# COBreplacement.net
KiCad netlist of a schematic drawn in EAGLE
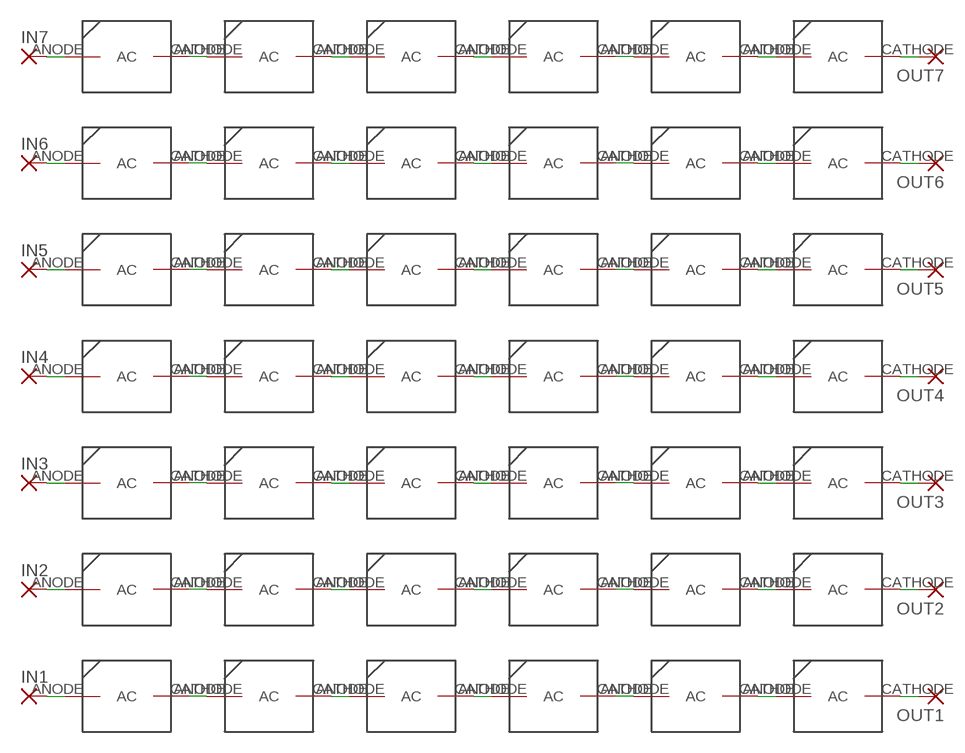
[diagram p0: schematic, sheet 1]

(export (version "E")
  (design (tool "Eeschema 10.0.6"))
  (components
    (comp (ref "IN1")
      (value "SMD2")
      (footprint "eagle-import:SMD1,27-2,54")
      (libsource (lib "eagle-import") (part "SMD2"))
    )
    (comp (ref "IN2")
      (value "SMD2")
      (footprint "eagle-import:SMD1,27-2,54")
      (libsource (lib "eagle-import") (part "SMD2"))
    )
    (comp (ref "IN3")
      (value "SMD2")
      (footprint "eagle-import:SMD1,27-2,54")
      (libsource (lib "eagle-import") (part "SMD2"))
    )
    (comp (ref "IN4")
      (value "SMD2")
      (footprint "eagle-import:SMD1,27-2,54")
      (libsource (lib "eagle-import") (part "SMD2"))
    )
    (comp (ref "IN5")
      (value "SMD2")
      (footprint "eagle-import:SMD1,27-2,54")
      (libsource (lib "eagle-import") (part "SMD2"))
    )
    (comp (ref "IN6")
      (value "SMD2")
      (footprint "eagle-import:SMD1,27-2,54")
      (libsource (lib "eagle-import") (part "SMD2"))
    )
    (comp (ref "IN7")
      (value "SMD2")
      (footprint "eagle-import:SMD1,27-2,54")
      (libsource (lib "eagle-import") (part "SMD2"))
    )
    (comp (ref "OUT1")
      (value "SMD2")
      (footprint "eagle-import:SMD1,27-2,54")
      (libsource (lib "eagle-import") (part "SMD2"))
    )
    (comp (ref "OUT2")
      (value "SMD2")
      (footprint "eagle-import:SMD1,27-2,54")
      (libsource (lib "eagle-import") (part "SMD2"))
    )
    (comp (ref "OUT3")
      (value "SMD2")
      (footprint "eagle-import:SMD1,27-2,54")
      (libsource (lib "eagle-import") (part "SMD2"))
    )
    (comp (ref "OUT4")
      (value "SMD2")
      (footprint "eagle-import:SMD1,27-2,54")
      (libsource (lib "eagle-import") (part "SMD2"))
    )
    (comp (ref "OUT5")
      (value "SMD2")
      (footprint "eagle-import:SMD1,27-2,54")
      (libsource (lib "eagle-import") (part "SMD2"))
    )
    (comp (ref "OUT6")
      (value "SMD2")
      (footprint "eagle-import:SMD1,27-2,54")
      (libsource (lib "eagle-import") (part "SMD2"))
    )
    (comp (ref "OUT7")
      (value "SMD2")
      (footprint "eagle-import:SMD1,27-2,54")
      (libsource (lib "eagle-import") (part "SMD2"))
    )
    (comp (ref "U$1")
      (value "XPE35LED")
      (footprint "eagle-import:XPE35")
      (libsource (lib "eagle-import") (part "XPE35LED"))
    )
    (comp (ref "U$2")
      (value "XPE35LED")
      (footprint "eagle-import:XPE35")
      (libsource (lib "eagle-import") (part "XPE35LED"))
    )
    (comp (ref "U$3")
      (value "XPE35LED")
      (footprint "eagle-import:XPE35")
      (libsource (lib "eagle-import") (part "XPE35LED"))
    )
    (comp (ref "U$4")
      (value "XPE35LED")
      (footprint "eagle-import:XPE35")
      (libsource (lib "eagle-import") (part "XPE35LED"))
    )
    (comp (ref "U$5")
      (value "XPE35LED")
      (footprint "eagle-import:XPE35")
      (libsource (lib "eagle-import") (part "XPE35LED"))
    )
    (comp (ref "U$6")
      (value "XPE35LED")
      (footprint "eagle-import:XPE35")
      (libsource (lib "eagle-import") (part "XPE35LED"))
    )
    (comp (ref "U$7")
      (value "XPE35LED")
      (footprint "eagle-import:XPE35")
      (libsource (lib "eagle-import") (part "XPE35LED"))
    )
    (comp (ref "U$8")
      (value "XPE35LED")
      (footprint "eagle-import:XPE35")
      (libsource (lib "eagle-import") (part "XPE35LED"))
    )
    (comp (ref "U$9")
      (value "XPE35LED")
      (footprint "eagle-import:XPE35")
      (libsource (lib "eagle-import") (part "XPE35LED"))
    )
    (comp (ref "U$10")
      (value "XPE35LED")
      (footprint "eagle-import:XPE35")
      (libsource (lib "eagle-import") (part "XPE35LED"))
    )
    (comp (ref "U$11")
      (value "XPE35LED")
      (footprint "eagle-import:XPE35")
      (libsource (lib "eagle-import") (part "XPE35LED"))
    )
    (comp (ref "U$12")
      (value "XPE35LED")
      (footprint "eagle-import:XPE35")
      (libsource (lib "eagle-import") (part "XPE35LED"))
    )
    (comp (ref "U$13")
      (value "XPE35LED")
      (footprint "eagle-import:XPE35")
      (libsource (lib "eagle-import") (part "XPE35LED"))
    )
    (comp (ref "U$14")
      (value "XPE35LED")
      (footprint "eagle-import:XPE35")
      (libsource (lib "eagle-import") (part "XPE35LED"))
    )
    (comp (ref "U$15")
      (value "XPE35LED")
      (footprint "eagle-import:XPE35")
      (libsource (lib "eagle-import") (part "XPE35LED"))
    )
    (comp (ref "U$16")
      (value "XPE35LED")
      (footprint "eagle-import:XPE35")
      (libsource (lib "eagle-import") (part "XPE35LED"))
    )
    (comp (ref "U$17")
      (value "XPE35LED")
      (footprint "eagle-import:XPE35")
      (libsource (lib "eagle-import") (part "XPE35LED"))
    )
    (comp (ref "U$18")
      (value "XPE35LED")
      (footprint "eagle-import:XPE35")
      (libsource (lib "eagle-import") (part "XPE35LED"))
    )
    (comp (ref "U$19")
      (value "XPE35LED")
      (footprint "eagle-import:XPE35")
      (libsource (lib "eagle-import") (part "XPE35LED"))
    )
    (comp (ref "U$20")
      (value "XPE35LED")
      (footprint "eagle-import:XPE35")
      (libsource (lib "eagle-import") (part "XPE35LED"))
    )
    (comp (ref "U$21")
      (value "XPE35LED")
      (footprint "eagle-import:XPE35")
      (libsource (lib "eagle-import") (part "XPE35LED"))
    )
    (comp (ref "U$22")
      (value "XPE35LED")
      (footprint "eagle-import:XPE35")
      (libsource (lib "eagle-import") (part "XPE35LED"))
    )
    (comp (ref "U$23")
      (value "XPE35LED")
      (footprint "eagle-import:XPE35")
      (libsource (lib "eagle-import") (part "XPE35LED"))
    )
    (comp (ref "U$24")
      (value "XPE35LED")
      (footprint "eagle-import:XPE35")
      (libsource (lib "eagle-import") (part "XPE35LED"))
    )
    (comp (ref "U$25")
      (value "XPE35LED")
      (footprint "eagle-import:XPE35")
      (libsource (lib "eagle-import") (part "XPE35LED"))
    )
    (comp (ref "U$26")
      (value "XPE35LED")
      (footprint "eagle-import:XPE35")
      (libsource (lib "eagle-import") (part "XPE35LED"))
    )
    (comp (ref "U$27")
      (value "XPE35LED")
      (footprint "eagle-import:XPE35")
      (libsource (lib "eagle-import") (part "XPE35LED"))
    )
    (comp (ref "U$28")
      (value "XPE35LED")
      (footprint "eagle-import:XPE35")
      (libsource (lib "eagle-import") (part "XPE35LED"))
    )
    (comp (ref "U$29")
      (value "XPE35LED")
      (footprint "eagle-import:XPE35")
      (libsource (lib "eagle-import") (part "XPE35LED"))
    )
    (comp (ref "U$30")
      (value "XPE35LED")
      (footprint "eagle-import:XPE35")
      (libsource (lib "eagle-import") (part "XPE35LED"))
    )
    (comp (ref "U$31")
      (value "XPE35LED")
      (footprint "eagle-import:XPE35")
      (libsource (lib "eagle-import") (part "XPE35LED"))
    )
    (comp (ref "U$32")
      (value "XPE35LED")
      (footprint "eagle-import:XPE35")
      (libsource (lib "eagle-import") (part "XPE35LED"))
    )
    (comp (ref "U$33")
      (value "XPE35LED")
      (footprint "eagle-import:XPE35")
      (libsource (lib "eagle-import") (part "XPE35LED"))
    )
    (comp (ref "U$34")
      (value "XPE35LED")
      (footprint "eagle-import:XPE35")
      (libsource (lib "eagle-import") (part "XPE35LED"))
    )
    (comp (ref "U$35")
      (value "XPE35LED")
      (footprint "eagle-import:XPE35")
      (libsource (lib "eagle-import") (part "XPE35LED"))
    )
    (comp (ref "U$36")
      (value "XPE35LED")
      (footprint "eagle-import:XPE35")
      (libsource (lib "eagle-import") (part "XPE35LED"))
    )
    (comp (ref "U$37")
      (value "XPE35LED")
      (footprint "eagle-import:XPE35")
      (libsource (lib "eagle-import") (part "XPE35LED"))
    )
    (comp (ref "U$38")
      (value "XPE35LED")
      (footprint "eagle-import:XPE35")
      (libsource (lib "eagle-import") (part "XPE35LED"))
    )
    (comp (ref "U$39")
      (value "XPE35LED")
      (footprint "eagle-import:XPE35")
      (libsource (lib "eagle-import") (part "XPE35LED"))
    )
    (comp (ref "U$40")
      (value "XPE35LED")
      (footprint "eagle-import:XPE35")
      (libsource (lib "eagle-import") (part "XPE35LED"))
    )
    (comp (ref "U$41")
      (value "XPE35LED")
      (footprint "eagle-import:XPE35")
      (libsource (lib "eagle-import") (part "XPE35LED"))
    )
    (comp (ref "U$42")
      (value "XPE35LED")
      (footprint "eagle-import:XPE35")
      (libsource (lib "eagle-import") (part "XPE35LED"))
    )
  )
  (nets
    (net (code "1") (name "Net-(IN1-P)") (class "Default")
      (node (ref "IN1") (pin "1") (pinfunction "P_1") (pintype "passive"))
      (node (ref "U$31") (pin "ANODE") (pinfunction "A_ANODE") (pintype "bidirectional"))
    )
    (net (code "2") (name "Net-(IN2-P)") (class "Default")
      (node (ref "IN2") (pin "1") (pinfunction "P_1") (pintype "passive"))
      (node (ref "U$25") (pin "ANODE") (pinfunction "A_ANODE") (pintype "bidirectional"))
    )
    (net (code "3") (name "Net-(IN3-P)") (class "Default")
      (node (ref "IN3") (pin "1") (pinfunction "P_1") (pintype "passive"))
      (node (ref "U$19") (pin "ANODE") (pinfunction "A_ANODE") (pintype "bidirectional"))
    )
    (net (code "4") (name "Net-(IN4-P)") (class "Default")
      (node (ref "IN4") (pin "1") (pinfunction "P_1") (pintype "passive"))
      (node (ref "U$13") (pin "ANODE") (pinfunction "A_ANODE") (pintype "bidirectional"))
    )
    (net (code "5") (name "Net-(IN5-P)") (class "Default")
      (node (ref "IN5") (pin "1") (pinfunction "P_1") (pintype "passive"))
      (node (ref "U$7") (pin "ANODE") (pinfunction "A_ANODE") (pintype "bidirectional"))
    )
    (net (code "6") (name "Net-(IN6-P)") (class "Default")
      (node (ref "IN6") (pin "1") (pinfunction "P_1") (pintype "passive"))
      (node (ref "U$1") (pin "ANODE") (pinfunction "A_ANODE") (pintype "bidirectional"))
    )
    (net (code "7") (name "Net-(IN7-P)") (class "Default")
      (node (ref "IN7") (pin "1") (pinfunction "P_1") (pintype "passive"))
      (node (ref "U$37") (pin "ANODE") (pinfunction "A_ANODE") (pintype "bidirectional"))
    )
    (net (code "8") (name "Net-(OUT1-P)") (class "Default")
      (node (ref "OUT1") (pin "1") (pinfunction "P_1") (pintype "passive"))
      (node (ref "U$36") (pin "CATHODE") (pinfunction "C_CATHODE") (pintype "bidirectional"))
    )
    (net (code "9") (name "Net-(OUT2-P)") (class "Default")
      (node (ref "OUT2") (pin "1") (pinfunction "P_1") (pintype "passive"))
      (node (ref "U$30") (pin "CATHODE") (pinfunction "C_CATHODE") (pintype "bidirectional"))
    )
    (net (code "10") (name "Net-(OUT3-P)") (class "Default")
      (node (ref "OUT3") (pin "1") (pinfunction "P_1") (pintype "passive"))
      (node (ref "U$24") (pin "CATHODE") (pinfunction "C_CATHODE") (pintype "bidirectional"))
    )
    (net (code "11") (name "Net-(OUT4-P)") (class "Default")
      (node (ref "OUT4") (pin "1") (pinfunction "P_1") (pintype "passive"))
      (node (ref "U$18") (pin "CATHODE") (pinfunction "C_CATHODE") (pintype "bidirectional"))
    )
    (net (code "12") (name "Net-(OUT5-P)") (class "Default")
      (node (ref "OUT5") (pin "1") (pinfunction "P_1") (pintype "passive"))
      (node (ref "U$12") (pin "CATHODE") (pinfunction "C_CATHODE") (pintype "bidirectional"))
    )
    (net (code "13") (name "Net-(OUT6-P)") (class "Default")
      (node (ref "OUT6") (pin "1") (pinfunction "P_1") (pintype "passive"))
      (node (ref "U$6") (pin "CATHODE") (pinfunction "C_CATHODE") (pintype "bidirectional"))
    )
    (net (code "14") (name "Net-(OUT7-P)") (class "Default")
      (node (ref "OUT7") (pin "1") (pinfunction "P_1") (pintype "passive"))
      (node (ref "U$42") (pin "CATHODE") (pinfunction "C_CATHODE") (pintype "bidirectional"))
    )
    (net (code "15") (name "Net-(U$1-C)") (class "Default")
      (node (ref "U$1") (pin "CATHODE") (pinfunction "C_CATHODE") (pintype "bidirectional"))
      (node (ref "U$2") (pin "ANODE") (pinfunction "A_ANODE") (pintype "bidirectional"))
    )
    (net (code "16") (name "Net-(U$2-C)") (class "Default")
      (node (ref "U$2") (pin "CATHODE") (pinfunction "C_CATHODE") (pintype "bidirectional"))
      (node (ref "U$3") (pin "ANODE") (pinfunction "A_ANODE") (pintype "bidirectional"))
    )
    (net (code "17") (name "Net-(U$3-C)") (class "Default")
      (node (ref "U$3") (pin "CATHODE") (pinfunction "C_CATHODE") (pintype "bidirectional"))
      (node (ref "U$4") (pin "ANODE") (pinfunction "A_ANODE") (pintype "bidirectional"))
    )
    (net (code "18") (name "Net-(U$4-C)") (class "Default")
      (node (ref "U$4") (pin "CATHODE") (pinfunction "C_CATHODE") (pintype "bidirectional"))
      (node (ref "U$5") (pin "ANODE") (pinfunction "A_ANODE") (pintype "bidirectional"))
    )
    (net (code "19") (name "Net-(U$5-C)") (class "Default")
      (node (ref "U$5") (pin "CATHODE") (pinfunction "C_CATHODE") (pintype "bidirectional"))
      (node (ref "U$6") (pin "ANODE") (pinfunction "A_ANODE") (pintype "bidirectional"))
    )
    (net (code "20") (name "Net-(U$7-C)") (class "Default")
      (node (ref "U$7") (pin "CATHODE") (pinfunction "C_CATHODE") (pintype "bidirectional"))
      (node (ref "U$8") (pin "ANODE") (pinfunction "A_ANODE") (pintype "bidirectional"))
    )
    (net (code "21") (name "Net-(U$8-C)") (class "Default")
      (node (ref "U$8") (pin "CATHODE") (pinfunction "C_CATHODE") (pintype "bidirectional"))
      (node (ref "U$9") (pin "ANODE") (pinfunction "A_ANODE") (pintype "bidirectional"))
    )
    (net (code "22") (name "Net-(U$10-A)") (class "Default")
      (node (ref "U$10") (pin "ANODE") (pinfunction "A_ANODE") (pintype "bidirectional"))
      (node (ref "U$9") (pin "CATHODE") (pinfunction "C_CATHODE") (pintype "bidirectional"))
    )
    (net (code "23") (name "Net-(U$10-C)") (class "Default")
      (node (ref "U$10") (pin "CATHODE") (pinfunction "C_CATHODE") (pintype "bidirectional"))
      (node (ref "U$11") (pin "ANODE") (pinfunction "A_ANODE") (pintype "bidirectional"))
    )
    (net (code "24") (name "Net-(U$11-C)") (class "Default")
      (node (ref "U$11") (pin "CATHODE") (pinfunction "C_CATHODE") (pintype "bidirectional"))
      (node (ref "U$12") (pin "ANODE") (pinfunction "A_ANODE") (pintype "bidirectional"))
    )
    (net (code "25") (name "Net-(U$13-C)") (class "Default")
      (node (ref "U$13") (pin "CATHODE") (pinfunction "C_CATHODE") (pintype "bidirectional"))
      (node (ref "U$14") (pin "ANODE") (pinfunction "A_ANODE") (pintype "bidirectional"))
    )
    (net (code "26") (name "Net-(U$14-C)") (class "Default")
      (node (ref "U$14") (pin "CATHODE") (pinfunction "C_CATHODE") (pintype "bidirectional"))
      (node (ref "U$15") (pin "ANODE") (pinfunction "A_ANODE") (pintype "bidirectional"))
    )
    (net (code "27") (name "Net-(U$15-C)") (class "Default")
      (node (ref "U$15") (pin "CATHODE") (pinfunction "C_CATHODE") (pintype "bidirectional"))
      (node (ref "U$16") (pin "ANODE") (pinfunction "A_ANODE") (pintype "bidirectional"))
    )
    (net (code "28") (name "Net-(U$16-C)") (class "Default")
      (node (ref "U$16") (pin "CATHODE") (pinfunction "C_CATHODE") (pintype "bidirectional"))
      (node (ref "U$17") (pin "ANODE") (pinfunction "A_ANODE") (pintype "bidirectional"))
    )
    (net (code "29") (name "Net-(U$17-C)") (class "Default")
      (node (ref "U$17") (pin "CATHODE") (pinfunction "C_CATHODE") (pintype "bidirectional"))
      (node (ref "U$18") (pin "ANODE") (pinfunction "A_ANODE") (pintype "bidirectional"))
    )
    (net (code "30") (name "Net-(U$19-C)") (class "Default")
      (node (ref "U$19") (pin "CATHODE") (pinfunction "C_CATHODE") (pintype "bidirectional"))
      (node (ref "U$20") (pin "ANODE") (pinfunction "A_ANODE") (pintype "bidirectional"))
    )
    (net (code "31") (name "Net-(U$20-C)") (class "Default")
      (node (ref "U$20") (pin "CATHODE") (pinfunction "C_CATHODE") (pintype "bidirectional"))
      (node (ref "U$21") (pin "ANODE") (pinfunction "A_ANODE") (pintype "bidirectional"))
    )
    (net (code "32") (name "Net-(U$21-C)") (class "Default")
      (node (ref "U$21") (pin "CATHODE") (pinfunction "C_CATHODE") (pintype "bidirectional"))
      (node (ref "U$22") (pin "ANODE") (pinfunction "A_ANODE") (pintype "bidirectional"))
    )
    (net (code "33") (name "Net-(U$22-C)") (class "Default")
      (node (ref "U$22") (pin "CATHODE") (pinfunction "C_CATHODE") (pintype "bidirectional"))
      (node (ref "U$23") (pin "ANODE") (pinfunction "A_ANODE") (pintype "bidirectional"))
    )
    (net (code "34") (name "Net-(U$23-C)") (class "Default")
      (node (ref "U$23") (pin "CATHODE") (pinfunction "C_CATHODE") (pintype "bidirectional"))
      (node (ref "U$24") (pin "ANODE") (pinfunction "A_ANODE") (pintype "bidirectional"))
    )
    (net (code "35") (name "Net-(U$25-C)") (class "Default")
      (node (ref "U$25") (pin "CATHODE") (pinfunction "C_CATHODE") (pintype "bidirectional"))
      (node (ref "U$26") (pin "ANODE") (pinfunction "A_ANODE") (pintype "bidirectional"))
    )
    (net (code "36") (name "Net-(U$26-C)") (class "Default")
      (node (ref "U$26") (pin "CATHODE") (pinfunction "C_CATHODE") (pintype "bidirectional"))
      (node (ref "U$27") (pin "ANODE") (pinfunction "A_ANODE") (pintype "bidirectional"))
    )
    (net (code "37") (name "Net-(U$27-C)") (class "Default")
      (node (ref "U$27") (pin "CATHODE") (pinfunction "C_CATHODE") (pintype "bidirectional"))
      (node (ref "U$28") (pin "ANODE") (pinfunction "A_ANODE") (pintype "bidirectional"))
    )
    (net (code "38") (name "Net-(U$28-C)") (class "Default")
      (node (ref "U$28") (pin "CATHODE") (pinfunction "C_CATHODE") (pintype "bidirectional"))
      (node (ref "U$29") (pin "ANODE") (pinfunction "A_ANODE") (pintype "bidirectional"))
    )
    (net (code "39") (name "Net-(U$29-C)") (class "Default")
      (node (ref "U$29") (pin "CATHODE") (pinfunction "C_CATHODE") (pintype "bidirectional"))
      (node (ref "U$30") (pin "ANODE") (pinfunction "A_ANODE") (pintype "bidirectional"))
    )
    (net (code "40") (name "Net-(U$31-C)") (class "Default")
      (node (ref "U$31") (pin "CATHODE") (pinfunction "C_CATHODE") (pintype "bidirectional"))
      (node (ref "U$32") (pin "ANODE") (pinfunction "A_ANODE") (pintype "bidirectional"))
    )
    (net (code "41") (name "Net-(U$32-C)") (class "Default")
      (node (ref "U$32") (pin "CATHODE") (pinfunction "C_CATHODE") (pintype "bidirectional"))
      (node (ref "U$33") (pin "ANODE") (pinfunction "A_ANODE") (pintype "bidirectional"))
    )
    (net (code "42") (name "Net-(U$33-C)") (class "Default")
      (node (ref "U$33") (pin "CATHODE") (pinfunction "C_CATHODE") (pintype "bidirectional"))
      (node (ref "U$34") (pin "ANODE") (pinfunction "A_ANODE") (pintype "bidirectional"))
    )
    (net (code "43") (name "Net-(U$34-C)") (class "Default")
      (node (ref "U$34") (pin "CATHODE") (pinfunction "C_CATHODE") (pintype "bidirectional"))
      (node (ref "U$35") (pin "ANODE") (pinfunction "A_ANODE") (pintype "bidirectional"))
    )
    (net (code "44") (name "Net-(U$35-C)") (class "Default")
      (node (ref "U$35") (pin "CATHODE") (pinfunction "C_CATHODE") (pintype "bidirectional"))
      (node (ref "U$36") (pin "ANODE") (pinfunction "A_ANODE") (pintype "bidirectional"))
    )
    (net (code "45") (name "Net-(U$37-C)") (class "Default")
      (node (ref "U$37") (pin "CATHODE") (pinfunction "C_CATHODE") (pintype "bidirectional"))
      (node (ref "U$38") (pin "ANODE") (pinfunction "A_ANODE") (pintype "bidirectional"))
    )
    (net (code "46") (name "Net-(U$38-C)") (class "Default")
      (node (ref "U$38") (pin "CATHODE") (pinfunction "C_CATHODE") (pintype "bidirectional"))
      (node (ref "U$39") (pin "ANODE") (pinfunction "A_ANODE") (pintype "bidirectional"))
    )
    (net (code "47") (name "Net-(U$39-C)") (class "Default")
      (node (ref "U$39") (pin "CATHODE") (pinfunction "C_CATHODE") (pintype "bidirectional"))
      (node (ref "U$40") (pin "ANODE") (pinfunction "A_ANODE") (pintype "bidirectional"))
    )
    (net (code "48") (name "Net-(U$40-C)") (class "Default")
      (node (ref "U$40") (pin "CATHODE") (pinfunction "C_CATHODE") (pintype "bidirectional"))
      (node (ref "U$41") (pin "ANODE") (pinfunction "A_ANODE") (pintype "bidirectional"))
    )
    (net (code "49") (name "Net-(U$41-C)") (class "Default")
      (node (ref "U$41") (pin "CATHODE") (pinfunction "C_CATHODE") (pintype "bidirectional"))
      (node (ref "U$42") (pin "ANODE") (pinfunction "A_ANODE") (pintype "bidirectional"))
    )
  )
)
